# CS3_Schnittstelle_REV0100.net
KiCad netlist of a schematic drawn in EAGLE
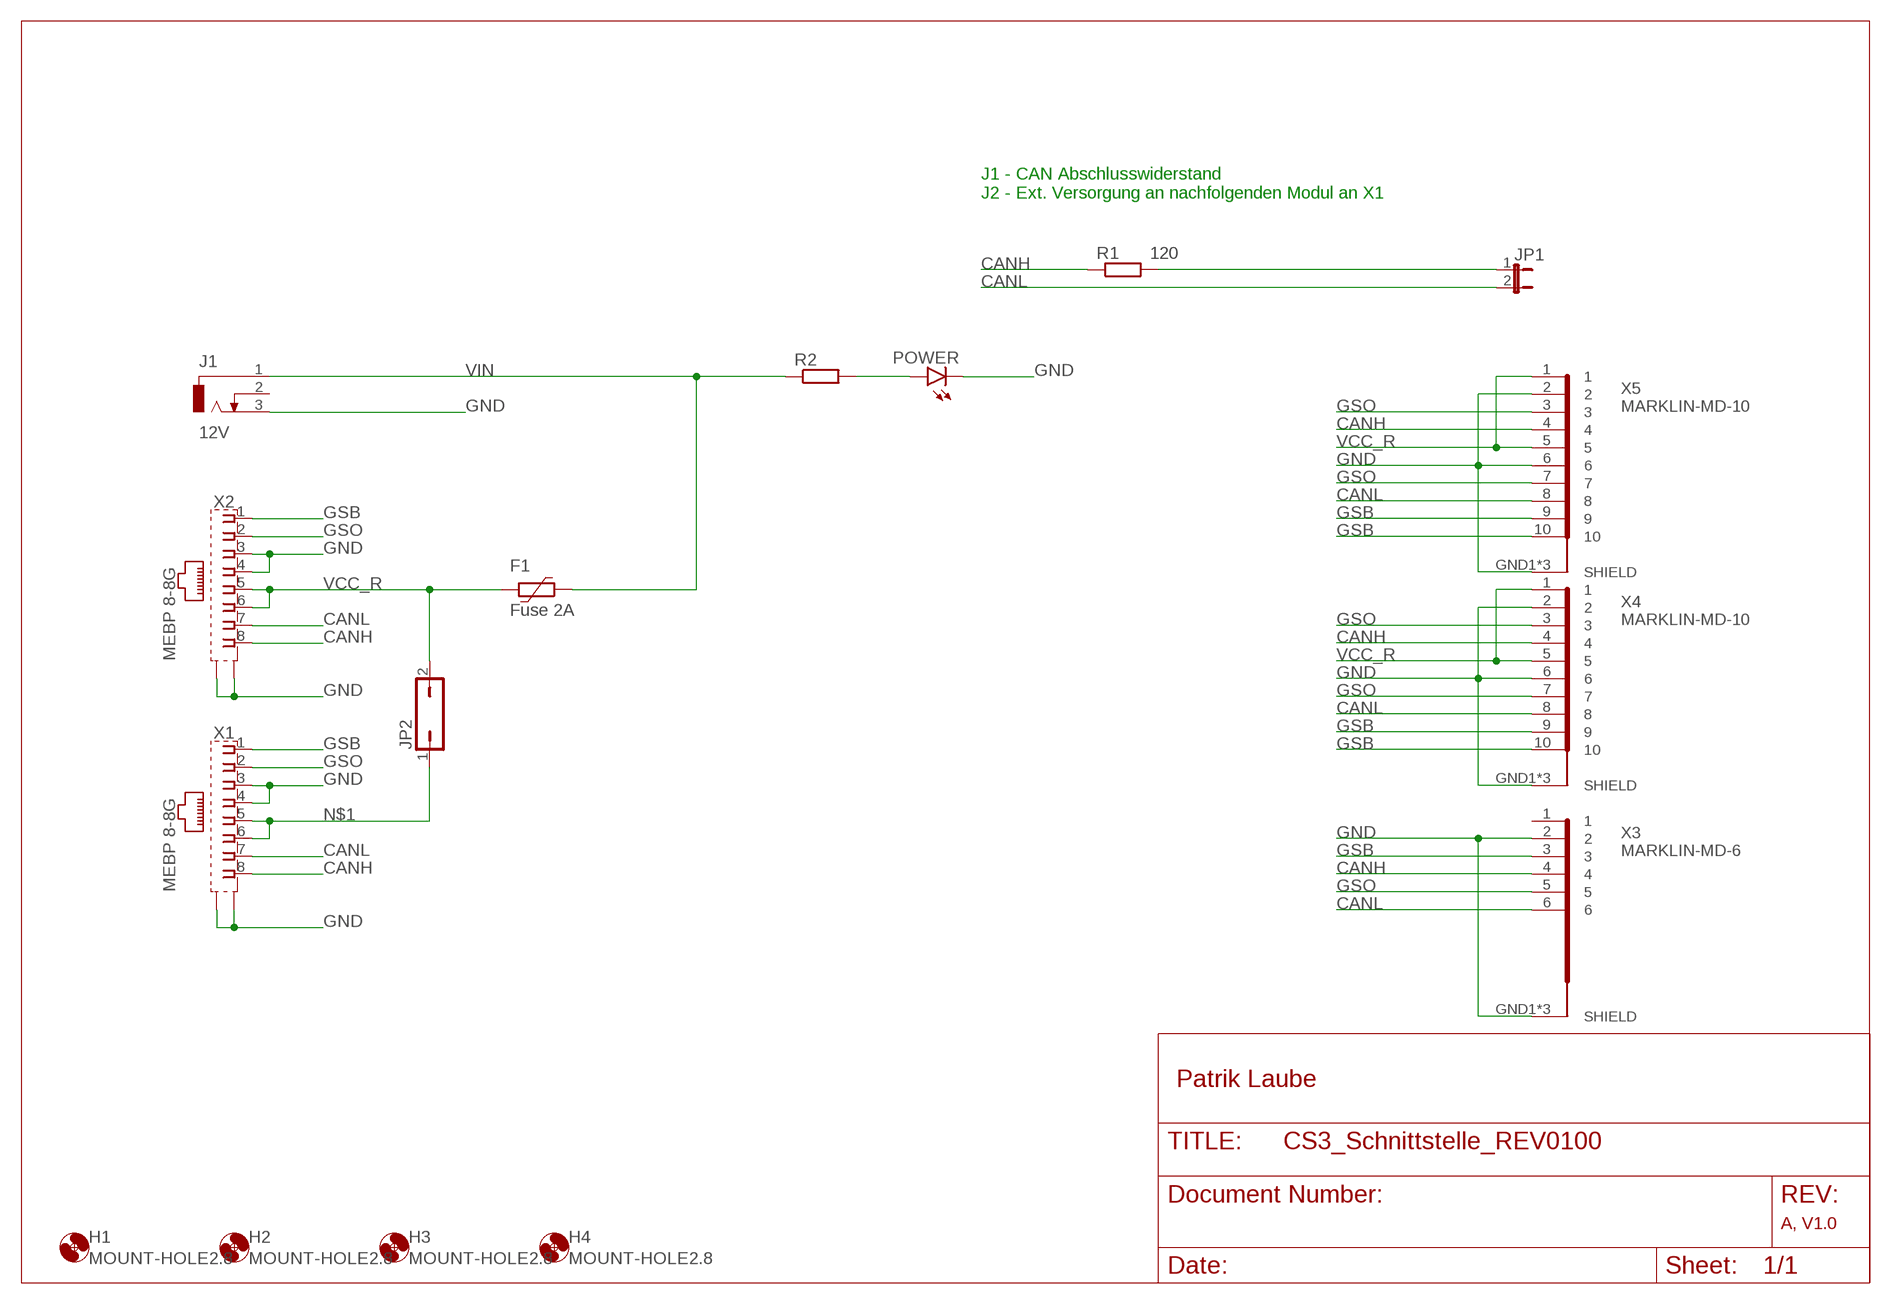
[diagram p0: schematic, sheet 1]

(export (version "E")
  (design (tool "Eeschema 10.0.6"))
  (components
    (comp (ref "F1")
      (value "Fuse 2A")
      (footprint "eagle-import:2920L")
      (fields (field (name "MF") "Littelfuse") (field (name "MPN") "2920L030"))
      (libsource (lib "eagle-import") (part "?2920L030"))
    )
    (comp (ref "H1")
      (value "MOUNT-HOLE2.8")
      (footprint "eagle-import:2,8")
      (libsource (lib "eagle-import") (part "MOUNT-HOLE2.8"))
    )
    (comp (ref "H2")
      (value "MOUNT-HOLE2.8")
      (footprint "eagle-import:2,8")
      (libsource (lib "eagle-import") (part "MOUNT-HOLE2.8"))
    )
    (comp (ref "H3")
      (value "MOUNT-HOLE2.8")
      (footprint "eagle-import:2,8")
      (libsource (lib "eagle-import") (part "MOUNT-HOLE2.8"))
    )
    (comp (ref "H4")
      (value "MOUNT-HOLE2.8")
      (footprint "eagle-import:2,8")
      (libsource (lib "eagle-import") (part "MOUNT-HOLE2.8"))
    )
    (comp (ref "J1")
      (value "12V")
      (footprint "eagle-import:DCJ0202")
      (libsource (lib "eagle-import") (part "DCJ0202"))
    )
    (comp (ref "JP1")
      (value "JP1E")
      (footprint "eagle-import:JP1")
      (libsource (lib "eagle-import") (part "JP1E"))
    )
    (comp (ref "JP2")
      (value "JP1Q")
      (footprint "eagle-import:JP1")
      (libsource (lib "eagle-import") (part "JP1Q"))
    )
    (comp (ref "POWER")
      (value "LEDCHIPLED_1206")
      (footprint "eagle-import:CHIPLED_1206")
      (libsource (lib "eagle-import") (part "LEDCHIPLED_1206"))
    )
    (comp (ref "R1")
      (value "120")
      (footprint "eagle-import:R1206")
      (libsource (lib "eagle-import") (part "R-EU_R1206"))
    )
    (comp (ref "R2")
      (value "R-EU_R1206")
      (footprint "eagle-import:R1206")
      (libsource (lib "eagle-import") (part "R-EU_R1206"))
    )
    (comp (ref "X1")
      (value "MEBP 8-8G")
      (footprint "eagle-import:XRJF-01A-0-D2A-010")
      (libsource (lib "eagle-import") (part "XRJFMEBP-8-8G-01A-0-D22-020"))
    )
    (comp (ref "X2")
      (value "MEBP 8-8G")
      (footprint "eagle-import:XRJF-01A-0-D2A-010")
      (libsource (lib "eagle-import") (part "XRJFMEBP-8-8G-01A-0-D22-020"))
    )
    (comp (ref "X3")
      (value "MARKLIN-MD-6")
      (footprint "eagle-import:MARKLIN-MD-6-PRINT")
      (libsource (lib "eagle-import") (part "MARKLIN-MD-6"))
    )
    (comp (ref "X4")
      (value "MARKLIN-MD-10")
      (footprint "eagle-import:MARKLIN-MD-10-PRINT")
      (libsource (lib "eagle-import") (part "MARKLIN-MD-10"))
    )
    (comp (ref "X5")
      (value "MARKLIN-MD-10")
      (footprint "eagle-import:MARKLIN-MD-10-PRINT")
      (libsource (lib "eagle-import") (part "MARKLIN-MD-10"))
    )
  )
  (nets
    (net (code "1") (name "/CANH") (class "Default")
      (node (ref "R1") (pin "1") (pinfunction "1_1") (pintype "passive"))
      (node (ref "X1") (pin "8") (pinfunction "8_8") (pintype "passive"))
      (node (ref "X2") (pin "8") (pinfunction "8_8") (pintype "passive"))
      (node (ref "X3") (pin "4") (pinfunction "4_4") (pintype "bidirectional"))
      (node (ref "X4") (pin "4") (pinfunction "4_4") (pintype "bidirectional"))
      (node (ref "X5") (pin "4") (pinfunction "4_4") (pintype "bidirectional"))
    )
    (net (code "2") (name "/CANL") (class "Default")
      (node (ref "JP1") (pin "2") (pinfunction "2_2") (pintype "passive"))
      (node (ref "X1") (pin "7") (pinfunction "7_7") (pintype "passive"))
      (node (ref "X2") (pin "7") (pinfunction "7_7") (pintype "passive"))
      (node (ref "X3") (pin "6") (pinfunction "6_6") (pintype "bidirectional"))
      (node (ref "X4") (pin "8") (pinfunction "8_8") (pintype "bidirectional"))
      (node (ref "X5") (pin "8") (pinfunction "8_8") (pintype "bidirectional"))
    )
    (net (code "3") (name "/GND") (class "Default")
      (node (ref "J1") (pin "3") (pinfunction "3_3") (pintype "passive"))
      (node (ref "POWER") (pin "C") (pinfunction "C_C") (pintype "passive"))
      (node (ref "X1") (pin "3") (pinfunction "3_3") (pintype "passive"))
      (node (ref "X1") (pin "4") (pinfunction "4_4") (pintype "passive"))
      (node (ref "X1") (pin "S1") (pinfunction "S_S1") (pintype "passive"))
      (node (ref "X1") (pin "S2") (pinfunction "S_S2") (pintype "passive"))
      (node (ref "X2") (pin "3") (pinfunction "3_3") (pintype "passive"))
      (node (ref "X2") (pin "4") (pinfunction "4_4") (pintype "passive"))
      (node (ref "X2") (pin "S1") (pinfunction "S_S1") (pintype "passive"))
      (node (ref "X2") (pin "S2") (pinfunction "S_S2") (pintype "passive"))
      (node (ref "X3") (pin "2") (pinfunction "2_2") (pintype "bidirectional"))
      (node (ref "X3") (pin "GND1") (pinfunction "SHIELD_GND1") (pintype "bidirectional"))
      (node (ref "X3") (pin "GND2") (pinfunction "SHIELD_GND2") (pintype "bidirectional"))
      (node (ref "X3") (pin "GND3") (pinfunction "SHIELD_GND3") (pintype "bidirectional"))
      (node (ref "X4") (pin "2") (pinfunction "2_2") (pintype "bidirectional"))
      (node (ref "X4") (pin "6") (pinfunction "6_6") (pintype "bidirectional"))
      (node (ref "X4") (pin "GND1") (pinfunction "SHIELD_GND1") (pintype "bidirectional"))
      (node (ref "X4") (pin "GND2") (pinfunction "SHIELD_GND2") (pintype "bidirectional"))
      (node (ref "X4") (pin "GND3") (pinfunction "SHIELD_GND3") (pintype "bidirectional"))
      (node (ref "X5") (pin "2") (pinfunction "2_2") (pintype "bidirectional"))
      (node (ref "X5") (pin "6") (pinfunction "6_6") (pintype "bidirectional"))
      (node (ref "X5") (pin "GND1") (pinfunction "SHIELD_GND1") (pintype "bidirectional"))
      (node (ref "X5") (pin "GND2") (pinfunction "SHIELD_GND2") (pintype "bidirectional"))
      (node (ref "X5") (pin "GND3") (pinfunction "SHIELD_GND3") (pintype "bidirectional"))
    )
    (net (code "4") (name "/GSB") (class "Default")
      (node (ref "X1") (pin "1") (pinfunction "1_1") (pintype "passive"))
      (node (ref "X2") (pin "1") (pinfunction "1_1") (pintype "passive"))
      (node (ref "X3") (pin "3") (pinfunction "3_3") (pintype "bidirectional"))
      (node (ref "X4") (pin "10") (pinfunction "10_10") (pintype "bidirectional"))
      (node (ref "X4") (pin "9") (pinfunction "9_9") (pintype "bidirectional"))
      (node (ref "X5") (pin "10") (pinfunction "10_10") (pintype "bidirectional"))
      (node (ref "X5") (pin "9") (pinfunction "9_9") (pintype "bidirectional"))
    )
    (net (code "5") (name "/GSO") (class "Default")
      (node (ref "X1") (pin "2") (pinfunction "2_2") (pintype "passive"))
      (node (ref "X2") (pin "2") (pinfunction "2_2") (pintype "passive"))
      (node (ref "X3") (pin "5") (pinfunction "5_5") (pintype "bidirectional"))
      (node (ref "X4") (pin "3") (pinfunction "3_3") (pintype "bidirectional"))
      (node (ref "X4") (pin "7") (pinfunction "7_7") (pintype "bidirectional"))
      (node (ref "X5") (pin "3") (pinfunction "3_3") (pintype "bidirectional"))
      (node (ref "X5") (pin "7") (pinfunction "7_7") (pintype "bidirectional"))
    )
    (net (code "6") (name "/N$1") (class "Default")
      (node (ref "JP2") (pin "1") (pinfunction "1_1") (pintype "passive"))
      (node (ref "X1") (pin "5") (pinfunction "5_5") (pintype "passive"))
      (node (ref "X1") (pin "6") (pinfunction "6_6") (pintype "passive"))
    )
    (net (code "7") (name "/VCC_R") (class "Default")
      (node (ref "F1") (pin "2") (pinfunction "2_2") (pintype "passive"))
      (node (ref "JP2") (pin "2") (pinfunction "2_2") (pintype "passive"))
      (node (ref "X2") (pin "5") (pinfunction "5_5") (pintype "passive"))
      (node (ref "X2") (pin "6") (pinfunction "6_6") (pintype "passive"))
      (node (ref "X4") (pin "1") (pinfunction "1_1") (pintype "bidirectional"))
      (node (ref "X4") (pin "5") (pinfunction "5_5") (pintype "bidirectional"))
      (node (ref "X5") (pin "1") (pinfunction "1_1") (pintype "bidirectional"))
      (node (ref "X5") (pin "5") (pinfunction "5_5") (pintype "bidirectional"))
    )
    (net (code "8") (name "/VIN") (class "Default")
      (node (ref "F1") (pin "1") (pinfunction "1_1") (pintype "passive"))
      (node (ref "J1") (pin "1") (pinfunction "1_1") (pintype "passive"))
      (node (ref "R2") (pin "1") (pinfunction "1_1") (pintype "passive"))
    )
    (net (code "9") (name "Net-(JP1-Pad1)") (class "Default")
      (node (ref "JP1") (pin "1") (pinfunction "1_1") (pintype "passive"))
      (node (ref "R1") (pin "2") (pinfunction "2_2") (pintype "passive"))
    )
    (net (code "10") (name "Net-(POWER-PadA)") (class "Default")
      (node (ref "POWER") (pin "A") (pinfunction "A_A") (pintype "passive"))
      (node (ref "R2") (pin "2") (pinfunction "2_2") (pintype "passive"))
    )
    (net (code "11") (name "unconnected-(J1-Pad2)") (class "Default")
      (node (ref "J1") (pin "2") (pinfunction "2_2") (pintype "passive"))
    )
    (net (code "12") (name "unconnected-(X3-Pad1)") (class "Default")
      (node (ref "X3") (pin "1") (pinfunction "1_1") (pintype "bidirectional"))
    )
  )
)
